# cap-test.net
KiCad netlist of a schematic drawn in Altium Designer
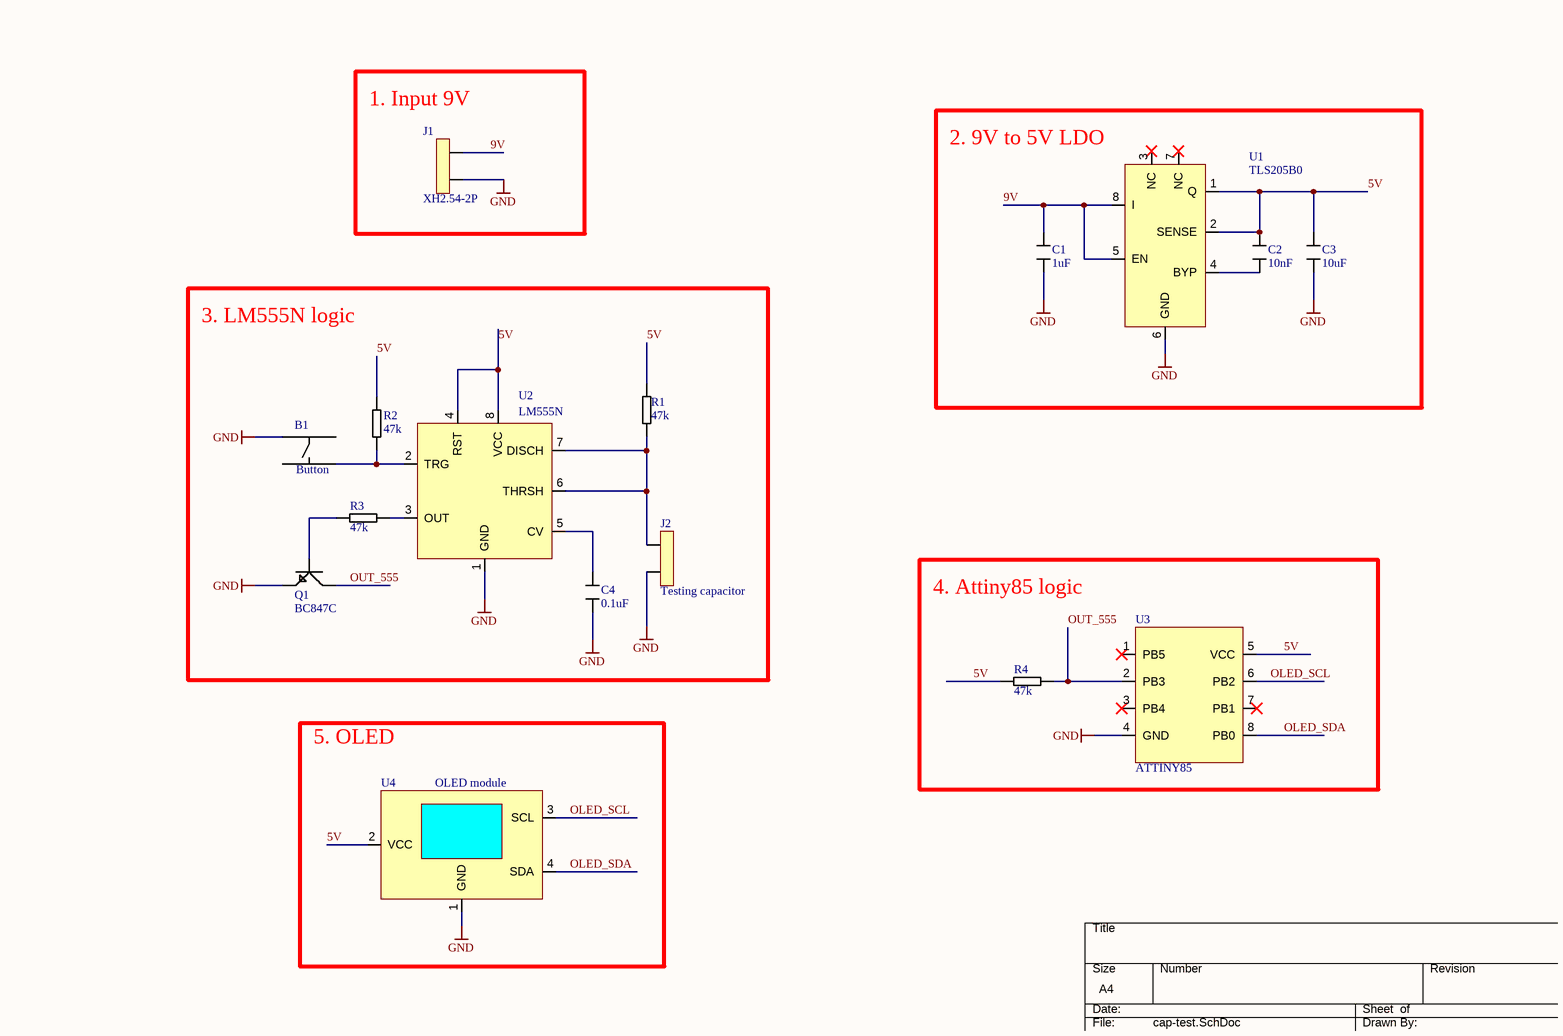
[diagram p0: cap-test.SchDoc]

(export (version "E")
  (design (tool "Eeschema 10.0.6"))
  (components
    (comp (ref "B1")
      (value "Button")
      (footprint "Button")
      (description "https://jlcpcb.com/partdetail/Yiyuan-YTS1R0032CBG00/C3001435")
      (libsource (lib "Schlib1") (part "Button"))
    )
    (comp (ref "C1") (value "1uF") (footprint "0603") (libsource (lib "Schlib1") (part "1uF")))
    (comp (ref "C2") (value "10nF") (footprint "0603") (libsource (lib "Schlib1") (part "10nF")))
    (comp (ref "C3") (value "10uF") (footprint "0603") (libsource (lib "Schlib1") (part "10uF")))
    (comp (ref "C4") (value "0.1uF") (footprint "0603") (libsource (lib "Schlib1") (part "0.1uF")))
    (comp (ref "J1")
      (value "XH2.54-2P")
      (footprint "XH2.54-2P")
      (libsource (lib "Schlib1") (part "XH2.54-2P"))
    )
    (comp (ref "J2")
      (value "Testing capacitor")
      (footprint "2.54mm header")
      (libsource (lib "Schlib1") (part "2.54mm pin header female"))
    )
    (comp (ref "Q1")
      (value "BC847C")
      (footprint "BC847C")
      (description "https://jlcpcb.com/partdetail/Hongjiacheng-BC847C/C7420337")
      (libsource (lib "Schlib1") (part "BC847C"))
    )
    (comp (ref "R1")
      (value "47k")
      (footprint "0603")
      (description "https://jlcpcb.com/partdetail/Walsin_TechCorp-WR06X4702FTL/C146207")
      (libsource (lib "") (part "47k_2"))
    )
    (comp (ref "R2")
      (value "47k")
      (footprint "0603")
      (description "https://jlcpcb.com/partdetail/Walsin_TechCorp-WR06X4702FTL/C146207")
      (libsource (lib "Schlib1") (part "47k"))
    )
    (comp (ref "R3")
      (value "47k")
      (footprint "0603")
      (description "https://jlcpcb.com/partdetail/Walsin_TechCorp-WR06X4702FTL/C146207")
      (libsource (lib "") (part "47k_1"))
    )
    (comp (ref "R4")
      (value "47k")
      (footprint "0603")
      (description "https://jlcpcb.com/partdetail/Walsin_TechCorp-WR06X4702FTL/C146207")
      (libsource (lib "") (part "47k_1"))
    )
    (comp (ref "U1") (value "TLS205B0") (footprint "TLS205B0") (libsource (lib "Schlib1") (part "TLS205B0")))
    (comp (ref "U2")
      (value "LM555N")
      (footprint "DIP8")
      (description "https://jlcpcb.com/partdetail/Hgsemi-LM555N/C725327")
      (libsource (lib "Schlib1") (part "LM555N"))
    )
    (comp (ref "U3")
      (value "ATTINY85")
      (footprint "DIP8")
      (description "https://jlcpcb.com/partdetail/MicrochipTech-ATTINY8520PU/C965497")
      (libsource (lib "Schlib1") (part "ATTINY85"))
    )
    (comp (ref "U4")
      (value "OLED module")
      (footprint "OLED module")
      (libsource (lib "Schlib1") (part "OLED module"))
    )
  )
  (nets
    (net (code "1") (name "/5V") (class "Default")
      (node (ref "C2") (pin "2") (pintype "passive"))
      (node (ref "C3") (pin "2") (pintype "passive"))
      (node (ref "R1") (pin "1") (pintype "passive"))
      (node (ref "R2") (pin "2") (pintype "passive"))
      (node (ref "R4") (pin "1") (pintype "passive"))
      (node (ref "U1") (pin "1") (pinfunction "Q_1") (pintype "passive"))
      (node (ref "U1") (pin "2") (pinfunction "SENSE_2") (pintype "passive"))
      (node (ref "U2") (pin "4") (pinfunction "RST_4") (pintype "passive"))
      (node (ref "U2") (pin "8") (pinfunction "VCC_8") (pintype "passive"))
      (node (ref "U3") (pin "5") (pinfunction "VCC_5") (pintype "passive"))
      (node (ref "U4") (pin "2") (pinfunction "VCC_2") (pintype "passive"))
    )
    (net (code "2") (name "/9V") (class "Default")
      (node (ref "C1") (pin "2") (pintype "passive"))
      (node (ref "J1") (pin "1") (pintype "passive"))
      (node (ref "U1") (pin "5") (pinfunction "EN_5") (pintype "passive"))
      (node (ref "U1") (pin "8") (pinfunction "I_8") (pintype "passive"))
    )
    (net (code "3") (name "/OLED_SCL") (class "Default")
      (node (ref "U3") (pin "6") (pinfunction "PB2_6") (pintype "passive"))
      (node (ref "U4") (pin "3") (pinfunction "SCL_3") (pintype "passive"))
    )
    (net (code "4") (name "/OLED_SDA") (class "Default")
      (node (ref "U3") (pin "8") (pinfunction "PB0_8") (pintype "passive"))
      (node (ref "U4") (pin "4") (pinfunction "SDA_4") (pintype "passive"))
    )
    (net (code "5") (name "/OUT_555") (class "Default")
      (node (ref "Q1") (pin "3") (pintype "passive"))
      (node (ref "R4") (pin "2") (pintype "passive"))
      (node (ref "U3") (pin "2") (pinfunction "PB3_2") (pintype "passive"))
    )
    (net (code "6") (name "GND") (class "Default")
      (node (ref "B1") (pin "1") (pintype "passive"))
      (node (ref "C1") (pin "1") (pintype "passive"))
      (node (ref "C3") (pin "1") (pintype "passive"))
      (node (ref "C4") (pin "1") (pintype "passive"))
      (node (ref "J1") (pin "2") (pintype "passive"))
      (node (ref "J2") (pin "1") (pintype "passive"))
      (node (ref "Q1") (pin "2") (pintype "passive"))
      (node (ref "U1") (pin "6") (pinfunction "GND_6") (pintype "passive"))
      (node (ref "U2") (pin "1") (pinfunction "GND_1") (pintype "passive"))
      (node (ref "U3") (pin "4") (pinfunction "GND_4") (pintype "passive"))
      (node (ref "U4") (pin "1") (pinfunction "GND_1") (pintype "passive"))
    )
    (net (code "7") (name "Net-(Q1-Pad1)") (class "Default")
      (node (ref "Q1") (pin "1") (pintype "passive"))
      (node (ref "R3") (pin "1") (pintype "passive"))
    )
    (net (code "8") (name "Net-(U1-BYP)") (class "Default")
      (node (ref "C2") (pin "1") (pintype "passive"))
      (node (ref "U1") (pin "4") (pinfunction "BYP_4") (pintype "passive"))
    )
    (net (code "9") (name "Net-(U2-CV)") (class "Default")
      (node (ref "C4") (pin "2") (pintype "passive"))
      (node (ref "U2") (pin "5") (pinfunction "CV_5") (pintype "passive"))
    )
    (net (code "10") (name "Net-(U2-DISCH)") (class "Default")
      (node (ref "J2") (pin "2") (pintype "passive"))
      (node (ref "R1") (pin "2") (pintype "passive"))
      (node (ref "U2") (pin "6") (pinfunction "THRSH_6") (pintype "passive"))
      (node (ref "U2") (pin "7") (pinfunction "DISCH_7") (pintype "passive"))
    )
    (net (code "11") (name "Net-(U2-OUT)") (class "Default")
      (node (ref "R3") (pin "2") (pintype "passive"))
      (node (ref "U2") (pin "3") (pinfunction "OUT_3") (pintype "passive"))
    )
    (net (code "12") (name "Net-(U2-TRG)") (class "Default")
      (node (ref "B1") (pin "4") (pintype "passive"))
      (node (ref "R2") (pin "1") (pintype "passive"))
      (node (ref "U2") (pin "2") (pinfunction "TRG_2") (pintype "passive"))
    )
    (net (code "13") (name "unconnected-(B1-Pad2)") (class "Default")
      (node (ref "B1") (pin "2") (pintype "passive"))
    )
    (net (code "14") (name "unconnected-(B1-Pad3)") (class "Default")
      (node (ref "B1") (pin "3") (pintype "passive"))
    )
    (net (code "15") (name "unconnected-(U1-NC-Pad3)") (class "Default")
      (node (ref "U1") (pin "3") (pinfunction "NC_3") (pintype "passive+no_connect"))
    )
    (net (code "16") (name "unconnected-(U1-NC-Pad7)") (class "Default")
      (node (ref "U1") (pin "7") (pinfunction "NC_7") (pintype "passive+no_connect"))
    )
    (net (code "17") (name "unconnected-(U3-PB1-Pad7)") (class "Default")
      (node (ref "U3") (pin "7") (pinfunction "PB1_7") (pintype "passive+no_connect"))
    )
    (net (code "18") (name "unconnected-(U3-PB4-Pad3)") (class "Default")
      (node (ref "U3") (pin "3") (pinfunction "PB4_3") (pintype "passive+no_connect"))
    )
    (net (code "19") (name "unconnected-(U3-PB5-Pad1)") (class "Default")
      (node (ref "U3") (pin "1") (pinfunction "PB5_1") (pintype "passive+no_connect"))
    )
  )
)
